# -TP2582_SR.net
KiCad netlist of a schematic drawn in EasyEDA Pro
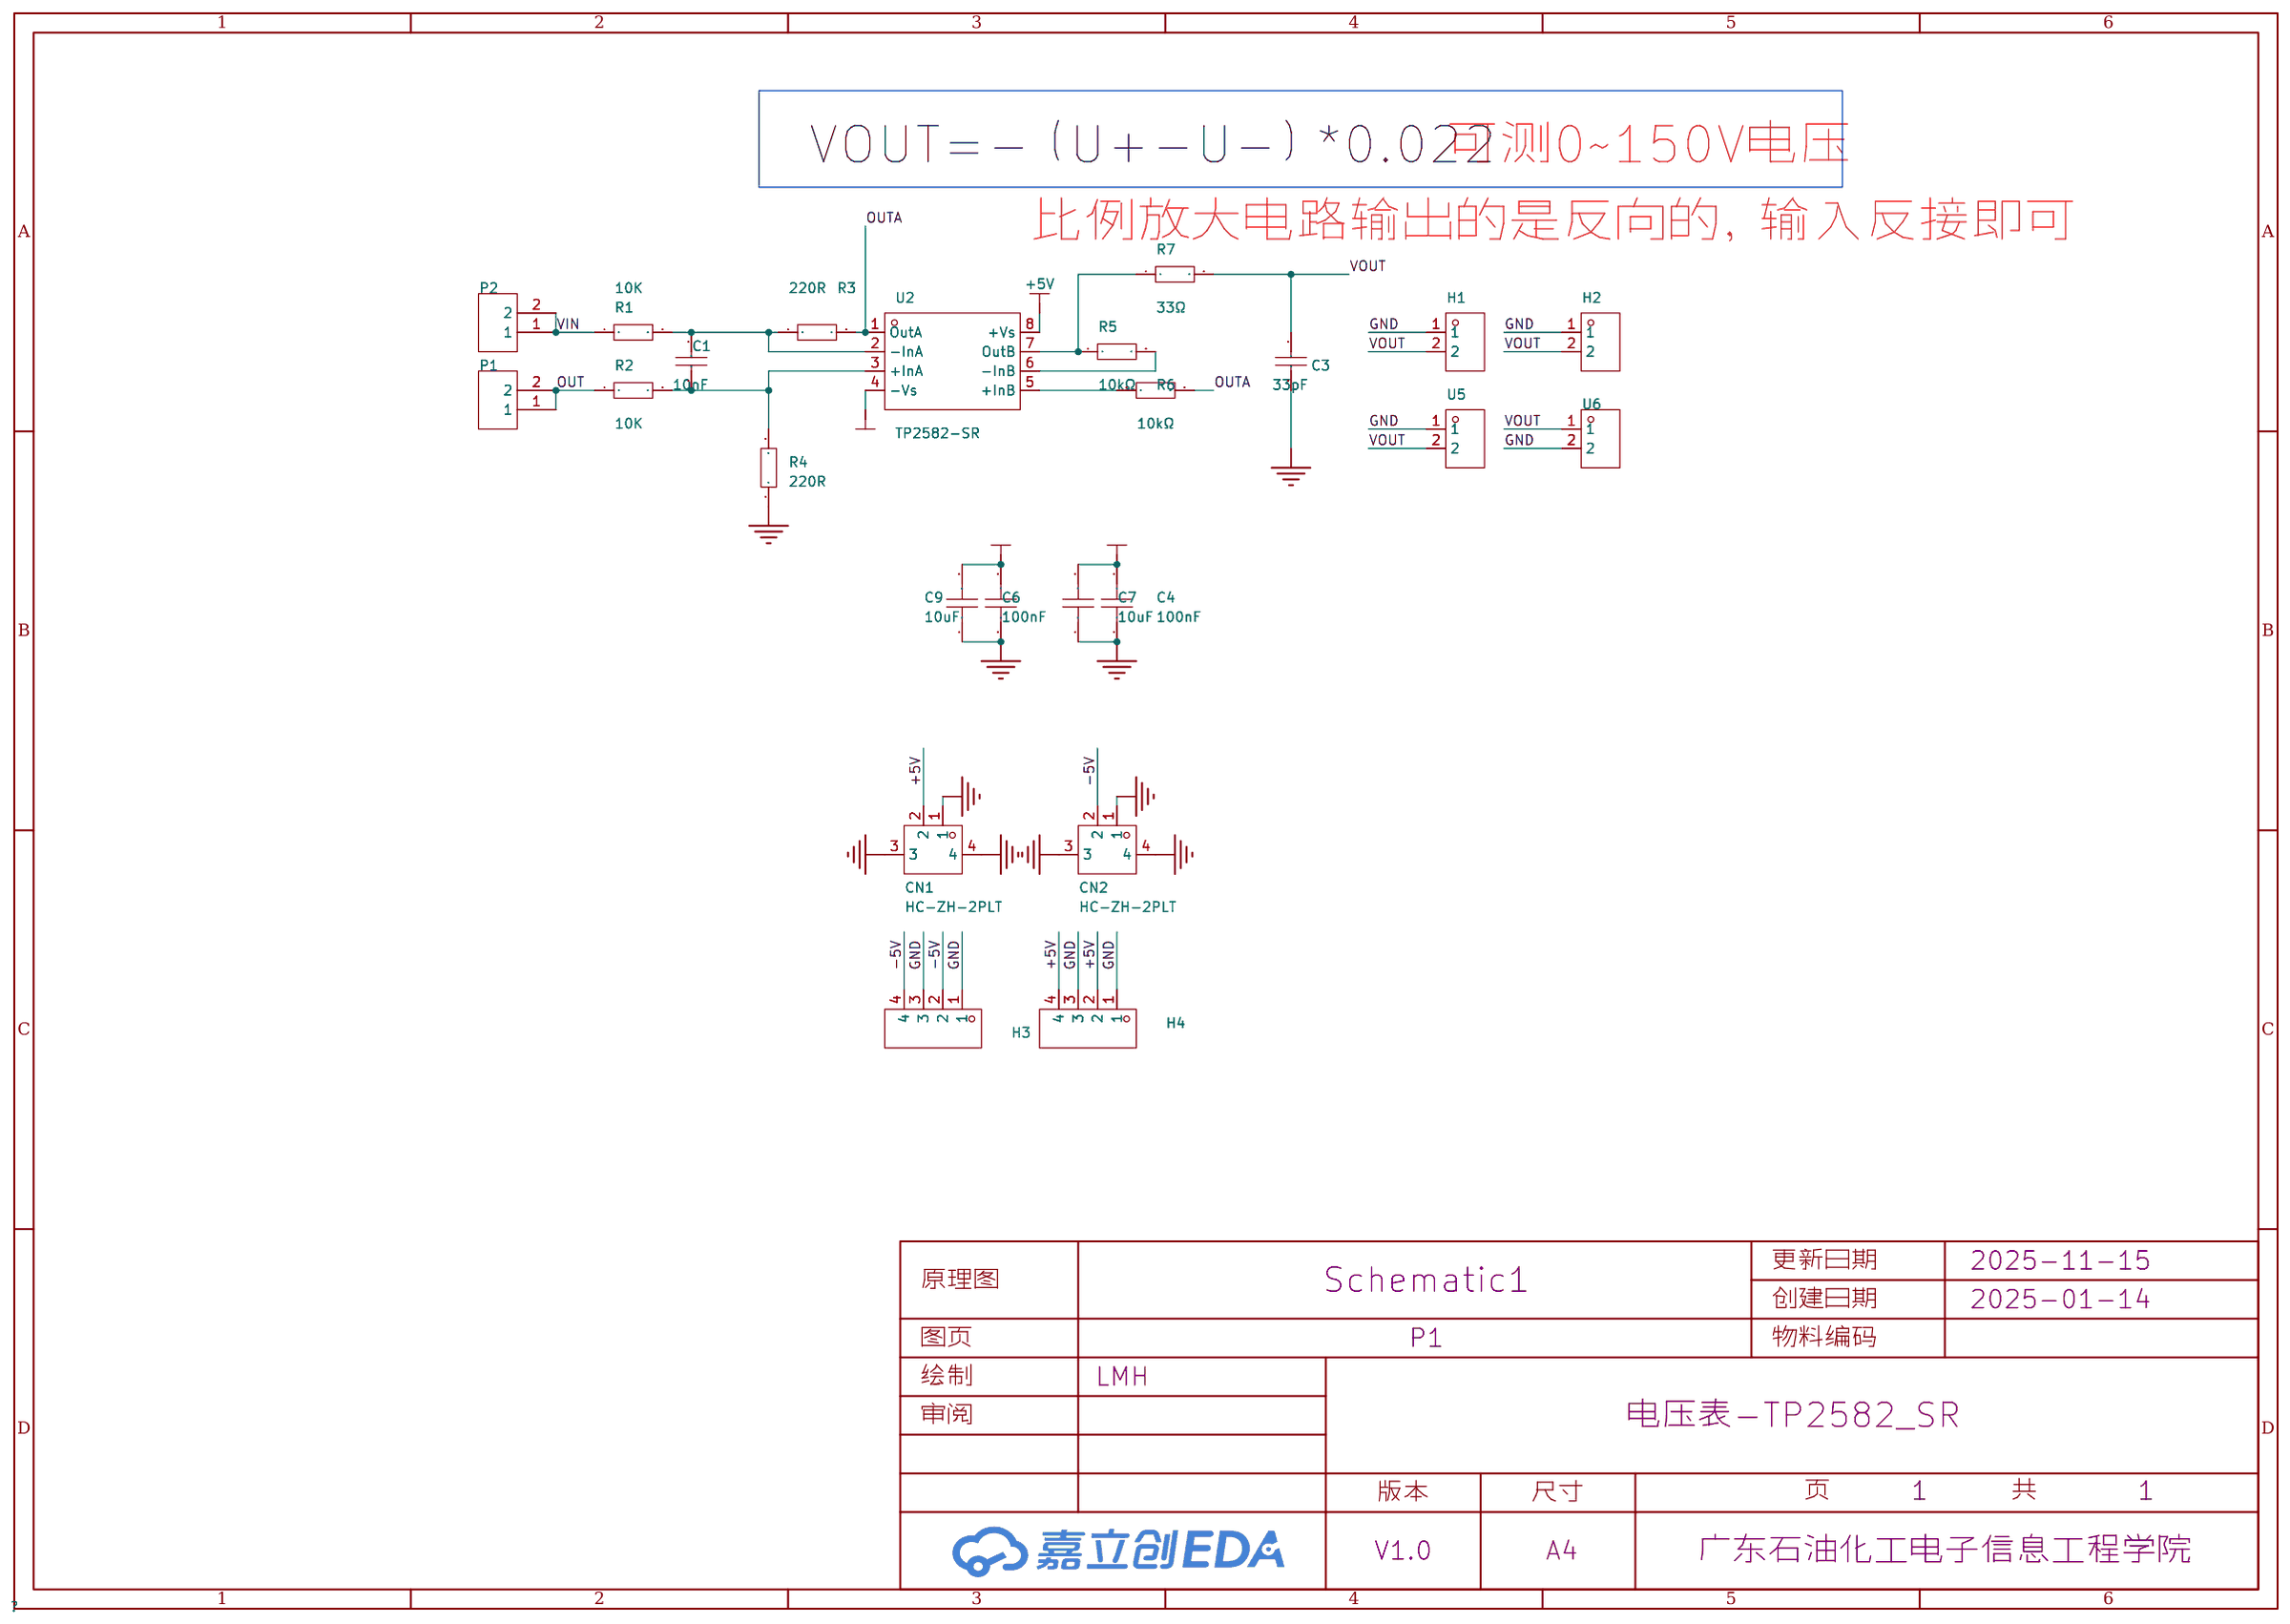
[diagram p0: schematic sheet]

(export (version "E")
  (design (tool "Eeschema 10.0.6"))
  (components
    (comp (ref "C1")
      (value "10nF")
      (footprint "easyedapro:C0805")
      (description "容值:10nF;精度:±10%;额定电压:50V;材质(温度系数):X7R;")
      (fields
        (field (name "Manufacturer Part") "CL21B103KBANNNC")
        (field (name "Manufacturer") "SAMSUNG(三星)")
      )
      (libsource (lib "easyedapro") (part "CL21B103KBANNNC"))
    )
    (comp (ref "C3")
      (value "33pF")
      (footprint "easyedapro:C0805")
      (description "容值:33pF;精度:±5%;额定电压:50V;材质(温度系数):NP0;")
      (fields
        (field (name "Manufacturer Part") "CC0805JRNPO9BN330")
        (field (name "Manufacturer") "YAGEO(国巨)")
      )
      (libsource (lib "easyedapro") (part "CC0805JRNPO9BN330"))
    )
    (comp (ref "C4")
      (value "100nF")
      (footprint "easyedapro:C0805")
      (description "容值:100nF;精度:±10%;额定电压:50V;材质(温度系数):X7R;")
      (fields
        (field (name "Manufacturer Part") "CC0805KRX7R9BB104")
        (field (name "Manufacturer") "YAGEO(国巨)")
      )
      (libsource (lib "easyedapro") (part "CC0805KRX7R9BB104"))
    )
    (comp (ref "C6")
      (value "100nF")
      (footprint "easyedapro:C0805")
      (description "容值:100nF;精度:±10%;额定电压:50V;材质(温度系数):X7R;")
      (fields
        (field (name "Manufacturer Part") "CC0805KRX7R9BB104")
        (field (name "Manufacturer") "YAGEO(国巨)")
      )
      (libsource (lib "easyedapro") (part "CC0805KRX7R9BB104"))
    )
    (comp (ref "C7")
      (value "10uF")
      (footprint "easyedapro:C0805")
      (description "容值:10uF;精度:±10%;额定电压:50V;材质(温度系数):X5R;")
      (fields
        (field (name "Manufacturer Part") "GRM21BR61H106KE43L")
        (field (name "Manufacturer") "muRata(村田)")
      )
      (libsource (lib "easyedapro") (part "GRM21BR61H106KE43L"))
    )
    (comp (ref "C9")
      (value "10uF")
      (footprint "easyedapro:C0805")
      (description "容值:10uF;精度:±10%;额定电压:50V;材质(温度系数):X5R;")
      (fields
        (field (name "Manufacturer Part") "GRM21BR61H106KE43L")
        (field (name "Manufacturer") "muRata(村田)")
      )
      (libsource (lib "easyedapro") (part "GRM21BR61H106KE43L"))
    )
    (comp (ref "CN1")
      (value "HC-ZH-2PLT")
      (footprint "easyedapro:CONN-SMD_2P-P1.5_HCTL_HC-ZH-2PLT")
      (fields (field (name "Manufacturer") "HCTL(华灿天禄)"))
      (libsource (lib "easyedapro") (part "HC-ZH-2PLT"))
    )
    (comp (ref "CN2")
      (value "HC-ZH-2PLT")
      (footprint "easyedapro:CONN-SMD_2P-P1.5_HCTL_HC-ZH-2PLT")
      (fields (field (name "Manufacturer") "HCTL(华灿天禄)"))
      (libsource (lib "easyedapro") (part "HC-ZH-2PLT"))
    )
    (comp (ref "H1")
      (value "PZ254V-11-02P")
      (footprint "easyedapro:HDR-TH_2P-P2.54-V-M")
      (fields (field (name "Manufacturer") "XFCN(兴飞)"))
      (libsource (lib "easyedapro") (part "PZ254V-11-02P"))
    )
    (comp (ref "H2")
      (value "PZ254V-11-02P")
      (footprint "easyedapro:HDR-TH_2P-P2.54-V-M")
      (fields (field (name "Manufacturer") "XFCN(兴飞)"))
      (libsource (lib "easyedapro") (part "PZ254V-11-02P"))
    )
    (comp (ref "H3")
      (value "PZ254V-11-04P")
      (footprint "easyedapro:HDR-TH_4P-P2.54-V-M")
      (fields (field (name "Manufacturer") "XFCN(兴飞)"))
      (libsource (lib "easyedapro") (part "PZ254V-11-04P_C2691448"))
    )
    (comp (ref "H4")
      (value "PZ254V-11-04P")
      (footprint "easyedapro:HDR-TH_4P-P2.54-V-M")
      (fields (field (name "Manufacturer") "XFCN(兴飞)"))
      (libsource (lib "easyedapro") (part "PZ254V-11-04P_C2691448"))
    )
    (comp (ref "P1")
      (value "WJ500V-5.08-2P")
      (footprint "easyedapro:CONN-TH_2P-P5.00_WJ500V-5.08-2P")
      (fields (field (name "Manufacturer") "KANGNEX(康奈克斯电气)"))
      (libsource (lib "easyedapro") (part "WJ500V-5.08-2P-14-00A"))
    )
    (comp (ref "P2")
      (value "WJ500V-5.08-2P")
      (footprint "easyedapro:CONN-TH_2P-P5.00_WJ500V-5.08-2P")
      (fields (field (name "Manufacturer") "KANGNEX(康奈克斯电气)"))
      (libsource (lib "easyedapro") (part "WJ500V-5.08-2P-14-00A"))
    )
    (comp (ref "R1")
      (value "10K")
      (footprint "easyedapro:R0805")
      (description "电阻类型:厚膜电阻;阻值:20kΩ;精度:±1%;功率:125mW;最大工作电压:150V;温度系数:±100ppm/°C;")
      (fields
        (field (name "Manufacturer Part") "0805W8F2002T5E")
        (field (name "Manufacturer") "UNI-ROYAL(厚声)")
      )
      (libsource (lib "easyedapro") (part "0805W8F2002T5E"))
    )
    (comp (ref "R2")
      (value "10K")
      (footprint "easyedapro:R0805")
      (description "电阻类型:厚膜电阻;阻值:20kΩ;精度:±1%;功率:125mW;最大工作电压:150V;温度系数:±100ppm/°C;")
      (fields
        (field (name "Manufacturer Part") "0805W8F2002T5E")
        (field (name "Manufacturer") "UNI-ROYAL(厚声)")
      )
      (libsource (lib "easyedapro") (part "0805W8F2002T5E"))
    )
    (comp (ref "R3")
      (value "220R")
      (footprint "easyedapro:R0805")
      (description "电阻类型:厚膜电阻;阻值:20kΩ;精度:±1%;功率:125mW;最大工作电压:150V;温度系数:±100ppm/°C;")
      (fields
        (field (name "Manufacturer Part") "0805W8F2002T5E")
        (field (name "Manufacturer") "UNI-ROYAL(厚声)")
      )
      (libsource (lib "easyedapro") (part "0805W8F2002T5E"))
    )
    (comp (ref "R4")
      (value "220R")
      (footprint "easyedapro:R0805")
      (description "电阻类型:厚膜电阻;阻值:20kΩ;精度:±1%;功率:125mW;最大工作电压:150V;温度系数:±100ppm/°C;")
      (fields
        (field (name "Manufacturer Part") "0805W8F2002T5E")
        (field (name "Manufacturer") "UNI-ROYAL(厚声)")
      )
      (libsource (lib "easyedapro") (part "0805W8F2002T5E"))
    )
    (comp (ref "R5")
      (value "10kΩ")
      (footprint "easyedapro:R0805")
      (description "电阻类型:厚膜电阻;阻值:10kΩ;精度:±1%;功率:125mW;最大工作电压:150V;温度系数:±100ppm/°C;")
      (fields
        (field (name "Manufacturer Part") "0805W8F1002T5E")
        (field (name "Manufacturer") "UNI-ROYAL(厚声)")
      )
      (libsource (lib "easyedapro") (part "0805W8F1002T5E"))
    )
    (comp (ref "R6")
      (value "10kΩ")
      (footprint "easyedapro:R0805")
      (description "电阻类型:厚膜电阻;阻值:10kΩ;精度:±1%;功率:125mW;最大工作电压:150V;温度系数:±100ppm/°C;")
      (fields
        (field (name "Manufacturer Part") "0805W8F1002T5E")
        (field (name "Manufacturer") "UNI-ROYAL(厚声)")
      )
      (libsource (lib "easyedapro") (part "0805W8F1002T5E"))
    )
    (comp (ref "R7")
      (value "33Ω")
      (footprint "easyedapro:R0805")
      (description "电阻类型:厚膜电阻;阻值:33Ω;精度:±1%;功率:125mW;最大工作电压:150V;温度系数:±200ppm/°C;")
      (fields
        (field (name "Manufacturer Part") "0805W8F330JT5E")
        (field (name "Manufacturer") "UNI-ROYAL(厚声)")
      )
      (libsource (lib "easyedapro") (part "0805W8F330JT5E"))
    )
    (comp (ref "U2")
      (value "TP2582-SR")
      (footprint "easyedapro:SOIC-8_L4.9-W3.9-P1.27-LS6.0-BL")
      (description "放大器数:双路;轨到轨:轨到轨输入,轨到轨输出;增益带宽积(GBP):10MHz;输入失调电压(Vos):3mV;压摆率(SR):8V/us;")
      (fields (field (name "Manufacturer") "3PEAK(思瑞浦)"))
      (libsource (lib "easyedapro") (part "TP2582-SR"))
    )
    (comp (ref "U5")
      (value "DB125-2.54-2P-GN-S")
      (footprint "easyedapro:CONN-TH_DB125-2.54-2P-GN")
      (fields (field (name "Manufacturer") "DORABO(地博电气)"))
      (libsource (lib "easyedapro") (part "DB125-2.54-2P-GN"))
    )
    (comp (ref "U6")
      (value "DB125-2.54-2P-GN-S")
      (footprint "easyedapro:CONN-TH_DB125-2.54-2P-GN")
      (fields (field (name "Manufacturer") "DORABO(地博电气)"))
      (libsource (lib "easyedapro") (part "DB125-2.54-2P-GN"))
    )
  )
  (nets
    (net (code "1") (name "+5V") (class "Default")
      (node (ref "C4") (pin "2") (pinfunction "2_2") (pintype "unspecified"))
      (node (ref "C7") (pin "2") (pinfunction "2_2") (pintype "unspecified"))
      (node (ref "CN1") (pin "2") (pinfunction "2_2") (pintype "unspecified"))
      (node (ref "H4") (pin "2") (pinfunction "2_2") (pintype "unspecified"))
      (node (ref "H4") (pin "4") (pinfunction "4_4") (pintype "unspecified"))
      (node (ref "U2") (pin "8") (pinfunction "+Vs_8") (pintype "unspecified"))
    )
    (net (code "2") (name "-5V") (class "Default")
      (node (ref "C6") (pin "2") (pinfunction "2_2") (pintype "unspecified"))
      (node (ref "C9") (pin "2") (pinfunction "2_2") (pintype "unspecified"))
      (node (ref "CN2") (pin "2") (pinfunction "2_2") (pintype "unspecified"))
      (node (ref "H3") (pin "2") (pinfunction "2_2") (pintype "unspecified"))
      (node (ref "H3") (pin "4") (pinfunction "4_4") (pintype "unspecified"))
      (node (ref "U2") (pin "4") (pinfunction "-Vs_4") (pintype "unspecified"))
    )
    (net (code "3") (name "/OUT") (class "Default")
      (node (ref "P1") (pin "1") (pinfunction "1_1") (pintype "unspecified"))
      (node (ref "P1") (pin "2") (pinfunction "2_2") (pintype "unspecified"))
      (node (ref "R2") (pin "1") (pinfunction "1_1") (pintype "input"))
    )
    (net (code "4") (name "/OUTA") (class "Default")
      (node (ref "R3") (pin "2") (pinfunction "2_2") (pintype "input"))
      (node (ref "R6") (pin "2") (pinfunction "2_2") (pintype "input"))
      (node (ref "U2") (pin "1") (pinfunction "OutA_1") (pintype "unspecified"))
    )
    (net (code "5") (name "/VIN") (class "Default")
      (node (ref "P2") (pin "1") (pinfunction "1_1") (pintype "unspecified"))
      (node (ref "P2") (pin "2") (pinfunction "2_2") (pintype "unspecified"))
      (node (ref "R1") (pin "1") (pinfunction "1_1") (pintype "input"))
    )
    (net (code "6") (name "/VOUT") (class "Default")
      (node (ref "C3") (pin "2") (pinfunction "2_2") (pintype "input"))
      (node (ref "H1") (pin "2") (pinfunction "2_2") (pintype "unspecified"))
      (node (ref "H2") (pin "2") (pinfunction "2_2") (pintype "unspecified"))
      (node (ref "R7") (pin "2") (pinfunction "2_2") (pintype "input"))
      (node (ref "U5") (pin "2") (pinfunction "2_2") (pintype "unspecified"))
      (node (ref "U6") (pin "1") (pinfunction "1_1") (pintype "unspecified"))
    )
    (net (code "7") (name "GND") (class "Default")
      (node (ref "C3") (pin "1") (pinfunction "1_1") (pintype "input"))
      (node (ref "C4") (pin "1") (pinfunction "1_1") (pintype "unspecified"))
      (node (ref "C6") (pin "1") (pinfunction "1_1") (pintype "unspecified"))
      (node (ref "C7") (pin "1") (pinfunction "1_1") (pintype "unspecified"))
      (node (ref "C9") (pin "1") (pinfunction "1_1") (pintype "unspecified"))
      (node (ref "CN1") (pin "1") (pinfunction "1_1") (pintype "unspecified"))
      (node (ref "CN1") (pin "3") (pinfunction "3_3") (pintype "unspecified"))
      (node (ref "CN1") (pin "4") (pinfunction "4_4") (pintype "unspecified"))
      (node (ref "CN2") (pin "1") (pinfunction "1_1") (pintype "unspecified"))
      (node (ref "CN2") (pin "3") (pinfunction "3_3") (pintype "unspecified"))
      (node (ref "CN2") (pin "4") (pinfunction "4_4") (pintype "unspecified"))
      (node (ref "H1") (pin "1") (pinfunction "1_1") (pintype "unspecified"))
      (node (ref "H2") (pin "1") (pinfunction "1_1") (pintype "unspecified"))
      (node (ref "H3") (pin "1") (pinfunction "1_1") (pintype "unspecified"))
      (node (ref "H3") (pin "3") (pinfunction "3_3") (pintype "unspecified"))
      (node (ref "H4") (pin "1") (pinfunction "1_1") (pintype "unspecified"))
      (node (ref "H4") (pin "3") (pinfunction "3_3") (pintype "unspecified"))
      (node (ref "R4") (pin "1") (pinfunction "1_1") (pintype "input"))
      (node (ref "U5") (pin "1") (pinfunction "1_1") (pintype "unspecified"))
      (node (ref "U6") (pin "2") (pinfunction "2_2") (pintype "unspecified"))
    )
    (net (code "8") (name "Net-(U2-+InA)") (class "Default")
      (node (ref "C1") (pin "1") (pinfunction "1_1") (pintype "input"))
      (node (ref "R2") (pin "2") (pinfunction "2_2") (pintype "input"))
      (node (ref "R4") (pin "2") (pinfunction "2_2") (pintype "input"))
      (node (ref "U2") (pin "3") (pinfunction "+InA_3") (pintype "unspecified"))
    )
    (net (code "9") (name "Net-(U2-+InB)") (class "Default")
      (node (ref "R6") (pin "1") (pinfunction "1_1") (pintype "input"))
      (node (ref "U2") (pin "5") (pinfunction "+InB_5") (pintype "unspecified"))
    )
    (net (code "10") (name "Net-(U2--InA)") (class "Default")
      (node (ref "C1") (pin "2") (pinfunction "2_2") (pintype "input"))
      (node (ref "R1") (pin "2") (pinfunction "2_2") (pintype "input"))
      (node (ref "R3") (pin "1") (pinfunction "1_1") (pintype "input"))
      (node (ref "U2") (pin "2") (pinfunction "-InA_2") (pintype "unspecified"))
    )
    (net (code "11") (name "Net-(U2--InB)") (class "Default")
      (node (ref "R5") (pin "2") (pinfunction "2_2") (pintype "input"))
      (node (ref "U2") (pin "6") (pinfunction "-InB_6") (pintype "unspecified"))
    )
    (net (code "12") (name "Net-(U2-OutB)") (class "Default")
      (node (ref "R5") (pin "1") (pinfunction "1_1") (pintype "input"))
      (node (ref "R7") (pin "1") (pinfunction "1_1") (pintype "input"))
      (node (ref "U2") (pin "7") (pinfunction "OutB_7") (pintype "unspecified"))
    )
  )
)
